# pwm_driver.net
KiCad netlist of a schematic drawn in EAGLE
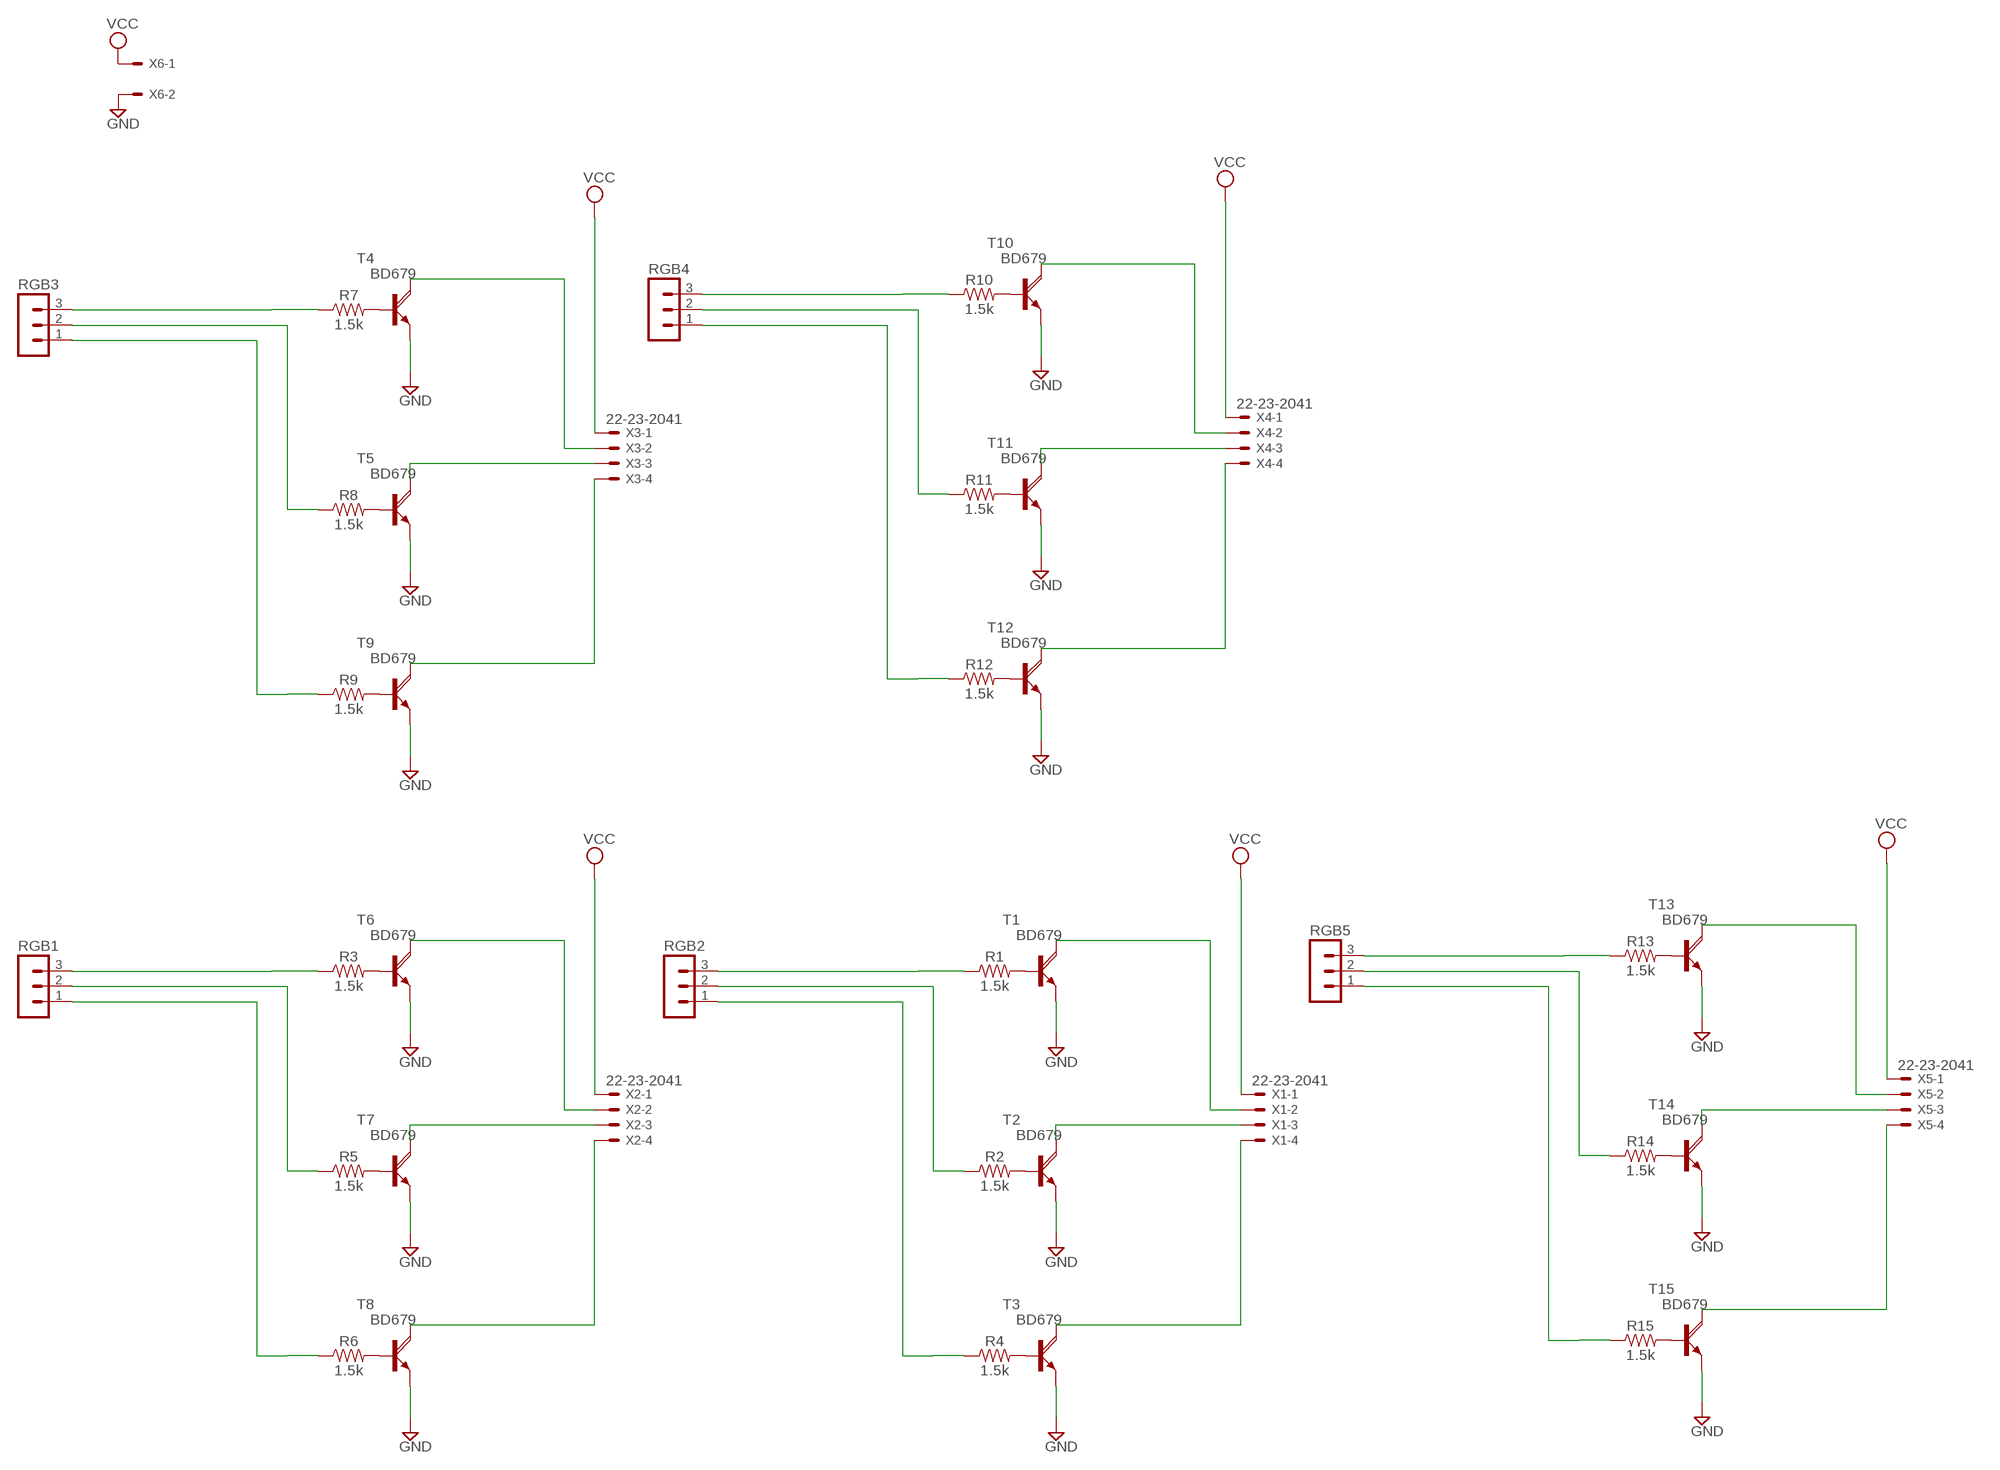
[diagram p0: schematic, sheet 1]

(export (version "E")
  (design (tool "Eeschema 10.0.6"))
  (components
    (comp (ref "R1")
      (value "1.5k")
      (footprint "eagle-import:0603")
      (libsource (lib "eagle-import") (part "1.5KOHM-0603-1/10W-1%"))
    )
    (comp (ref "R2")
      (value "1.5k")
      (footprint "eagle-import:0603")
      (libsource (lib "eagle-import") (part "1.5KOHM-0603-1/10W-1%"))
    )
    (comp (ref "R3")
      (value "1.5k")
      (footprint "eagle-import:0603")
      (libsource (lib "eagle-import") (part "1.5KOHM-0603-1/10W-1%"))
    )
    (comp (ref "R4")
      (value "1.5k")
      (footprint "eagle-import:0603")
      (libsource (lib "eagle-import") (part "1.5KOHM-0603-1/10W-1%"))
    )
    (comp (ref "R5")
      (value "1.5k")
      (footprint "eagle-import:0603")
      (libsource (lib "eagle-import") (part "1.5KOHM-0603-1/10W-1%"))
    )
    (comp (ref "R6")
      (value "1.5k")
      (footprint "eagle-import:0603")
      (libsource (lib "eagle-import") (part "1.5KOHM-0603-1/10W-1%"))
    )
    (comp (ref "R7")
      (value "1.5k")
      (footprint "eagle-import:0603")
      (libsource (lib "eagle-import") (part "1.5KOHM-0603-1/10W-1%"))
    )
    (comp (ref "R8")
      (value "1.5k")
      (footprint "eagle-import:0603")
      (libsource (lib "eagle-import") (part "1.5KOHM-0603-1/10W-1%"))
    )
    (comp (ref "R9")
      (value "1.5k")
      (footprint "eagle-import:0603")
      (libsource (lib "eagle-import") (part "1.5KOHM-0603-1/10W-1%"))
    )
    (comp (ref "R10")
      (value "1.5k")
      (footprint "eagle-import:0603")
      (libsource (lib "eagle-import") (part "1.5KOHM-0603-1/10W-1%"))
    )
    (comp (ref "R11")
      (value "1.5k")
      (footprint "eagle-import:0603")
      (libsource (lib "eagle-import") (part "1.5KOHM-0603-1/10W-1%"))
    )
    (comp (ref "R12")
      (value "1.5k")
      (footprint "eagle-import:0603")
      (libsource (lib "eagle-import") (part "1.5KOHM-0603-1/10W-1%"))
    )
    (comp (ref "R13")
      (value "1.5k")
      (footprint "eagle-import:0603")
      (libsource (lib "eagle-import") (part "1.5KOHM-0603-1/10W-1%"))
    )
    (comp (ref "R14")
      (value "1.5k")
      (footprint "eagle-import:0603")
      (libsource (lib "eagle-import") (part "1.5KOHM-0603-1/10W-1%"))
    )
    (comp (ref "R15")
      (value "1.5k")
      (footprint "eagle-import:0603")
      (libsource (lib "eagle-import") (part "1.5KOHM-0603-1/10W-1%"))
    )
    (comp (ref "RGB1")
      (value "MA03-1")
      (footprint "eagle-import:MA03-1")
      (libsource (lib "eagle-import") (part "MA03-1"))
    )
    (comp (ref "RGB2")
      (value "MA03-1")
      (footprint "eagle-import:MA03-1")
      (libsource (lib "eagle-import") (part "MA03-1"))
    )
    (comp (ref "RGB3")
      (value "MA03-1")
      (footprint "eagle-import:MA03-1")
      (libsource (lib "eagle-import") (part "MA03-1"))
    )
    (comp (ref "RGB4")
      (value "MA03-1")
      (footprint "eagle-import:MA03-1")
      (libsource (lib "eagle-import") (part "MA03-1"))
    )
    (comp (ref "RGB5")
      (value "MA03-1")
      (footprint "eagle-import:MA03-1")
      (libsource (lib "eagle-import") (part "MA03-1"))
    )
    (comp (ref "T1")
      (value "BD679")
      (footprint "eagle-import:TO126AV")
      (libsource (lib "eagle-import") (part "BD679"))
    )
    (comp (ref "T2")
      (value "BD679")
      (footprint "eagle-import:TO126AV")
      (libsource (lib "eagle-import") (part "BD679"))
    )
    (comp (ref "T3")
      (value "BD679")
      (footprint "eagle-import:TO126AV")
      (libsource (lib "eagle-import") (part "BD679"))
    )
    (comp (ref "T4")
      (value "BD679")
      (footprint "eagle-import:TO126AV")
      (libsource (lib "eagle-import") (part "BD679"))
    )
    (comp (ref "T5")
      (value "BD679")
      (footprint "eagle-import:TO126AV")
      (libsource (lib "eagle-import") (part "BD679"))
    )
    (comp (ref "T6")
      (value "BD679")
      (footprint "eagle-import:TO126AV")
      (libsource (lib "eagle-import") (part "BD679"))
    )
    (comp (ref "T7")
      (value "BD679")
      (footprint "eagle-import:TO126AV")
      (libsource (lib "eagle-import") (part "BD679"))
    )
    (comp (ref "T8")
      (value "BD679")
      (footprint "eagle-import:TO126AV")
      (libsource (lib "eagle-import") (part "BD679"))
    )
    (comp (ref "T9")
      (value "BD679")
      (footprint "eagle-import:TO126AV")
      (libsource (lib "eagle-import") (part "BD679"))
    )
    (comp (ref "T10")
      (value "BD679")
      (footprint "eagle-import:TO126AV")
      (libsource (lib "eagle-import") (part "BD679"))
    )
    (comp (ref "T11")
      (value "BD679")
      (footprint "eagle-import:TO126AV")
      (libsource (lib "eagle-import") (part "BD679"))
    )
    (comp (ref "T12")
      (value "BD679")
      (footprint "eagle-import:TO126AV")
      (libsource (lib "eagle-import") (part "BD679"))
    )
    (comp (ref "T13")
      (value "BD679")
      (footprint "eagle-import:TO126AV")
      (libsource (lib "eagle-import") (part "BD679"))
    )
    (comp (ref "T14")
      (value "BD679")
      (footprint "eagle-import:TO126AV")
      (libsource (lib "eagle-import") (part "BD679"))
    )
    (comp (ref "T15")
      (value "BD679")
      (footprint "eagle-import:TO126AV")
      (libsource (lib "eagle-import") (part "BD679"))
    )
    (comp (ref "X1")
      (value "22-23-2041")
      (footprint "eagle-import:22-23-2041")
      (fields (field (name "MF") "MOLEX"))
      (libsource (lib "eagle-import") (part "22-23-2041"))
    )
    (comp (ref "X2")
      (value "22-23-2041")
      (footprint "eagle-import:22-23-2041")
      (fields (field (name "MF") "MOLEX"))
      (libsource (lib "eagle-import") (part "22-23-2041"))
    )
    (comp (ref "X3")
      (value "22-23-2041")
      (footprint "eagle-import:22-23-2041")
      (fields (field (name "MF") "MOLEX"))
      (libsource (lib "eagle-import") (part "22-23-2041"))
    )
    (comp (ref "X4")
      (value "22-23-2041")
      (footprint "eagle-import:22-23-2041")
      (fields (field (name "MF") "MOLEX"))
      (libsource (lib "eagle-import") (part "22-23-2041"))
    )
    (comp (ref "X5")
      (value "22-23-2041")
      (footprint "eagle-import:22-23-2041")
      (fields (field (name "MF") "MOLEX"))
      (libsource (lib "eagle-import") (part "22-23-2041"))
    )
    (comp (ref "X6")
      (value "KK-156-2")
      (footprint "eagle-import:KK-156-2")
      (fields (field (name "MF") "MOLEX"))
      (libsource (lib "eagle-import") (part "KK-156-2"))
    )
  )
  (nets
    (net (code "1") (name "GND") (class "Default")
      (node (ref "T1") (pin "E") (pinfunction "E_E") (pintype "passive"))
      (node (ref "T10") (pin "E") (pinfunction "E_E") (pintype "passive"))
      (node (ref "T11") (pin "E") (pinfunction "E_E") (pintype "passive"))
      (node (ref "T12") (pin "E") (pinfunction "E_E") (pintype "passive"))
      (node (ref "T13") (pin "E") (pinfunction "E_E") (pintype "passive"))
      (node (ref "T14") (pin "E") (pinfunction "E_E") (pintype "passive"))
      (node (ref "T15") (pin "E") (pinfunction "E_E") (pintype "passive"))
      (node (ref "T2") (pin "E") (pinfunction "E_E") (pintype "passive"))
      (node (ref "T3") (pin "E") (pinfunction "E_E") (pintype "passive"))
      (node (ref "T4") (pin "E") (pinfunction "E_E") (pintype "passive"))
      (node (ref "T5") (pin "E") (pinfunction "E_E") (pintype "passive"))
      (node (ref "T6") (pin "E") (pinfunction "E_E") (pintype "passive"))
      (node (ref "T7") (pin "E") (pinfunction "E_E") (pintype "passive"))
      (node (ref "T8") (pin "E") (pinfunction "E_E") (pintype "passive"))
      (node (ref "T9") (pin "E") (pinfunction "E_E") (pintype "passive"))
      (node (ref "X6") (pin "2") (pinfunction "S_2") (pintype "passive"))
    )
    (net (code "2") (name "Net-(R1-Pad1)") (class "Default")
      (node (ref "R1") (pin "1") (pinfunction "1_1") (pintype "passive"))
      (node (ref "RGB2") (pin "3") (pinfunction "3_3") (pintype "passive"))
    )
    (net (code "3") (name "Net-(R1-Pad2)") (class "Default")
      (node (ref "R1") (pin "2") (pinfunction "2_2") (pintype "passive"))
      (node (ref "T1") (pin "B") (pinfunction "B_B") (pintype "passive"))
    )
    (net (code "4") (name "Net-(R2-Pad1)") (class "Default")
      (node (ref "R2") (pin "1") (pinfunction "1_1") (pintype "passive"))
      (node (ref "RGB2") (pin "2") (pinfunction "2_2") (pintype "passive"))
    )
    (net (code "5") (name "Net-(R2-Pad2)") (class "Default")
      (node (ref "R2") (pin "2") (pinfunction "2_2") (pintype "passive"))
      (node (ref "T2") (pin "B") (pinfunction "B_B") (pintype "passive"))
    )
    (net (code "6") (name "Net-(R3-Pad1)") (class "Default")
      (node (ref "R3") (pin "1") (pinfunction "1_1") (pintype "passive"))
      (node (ref "RGB1") (pin "3") (pinfunction "3_3") (pintype "passive"))
    )
    (net (code "7") (name "Net-(R3-Pad2)") (class "Default")
      (node (ref "R3") (pin "2") (pinfunction "2_2") (pintype "passive"))
      (node (ref "T6") (pin "B") (pinfunction "B_B") (pintype "passive"))
    )
    (net (code "8") (name "Net-(R4-Pad1)") (class "Default")
      (node (ref "R4") (pin "1") (pinfunction "1_1") (pintype "passive"))
      (node (ref "RGB2") (pin "1") (pinfunction "1_1") (pintype "passive"))
    )
    (net (code "9") (name "Net-(R4-Pad2)") (class "Default")
      (node (ref "R4") (pin "2") (pinfunction "2_2") (pintype "passive"))
      (node (ref "T3") (pin "B") (pinfunction "B_B") (pintype "passive"))
    )
    (net (code "10") (name "Net-(R5-Pad1)") (class "Default")
      (node (ref "R5") (pin "1") (pinfunction "1_1") (pintype "passive"))
      (node (ref "RGB1") (pin "2") (pinfunction "2_2") (pintype "passive"))
    )
    (net (code "11") (name "Net-(R5-Pad2)") (class "Default")
      (node (ref "R5") (pin "2") (pinfunction "2_2") (pintype "passive"))
      (node (ref "T7") (pin "B") (pinfunction "B_B") (pintype "passive"))
    )
    (net (code "12") (name "Net-(R6-Pad1)") (class "Default")
      (node (ref "R6") (pin "1") (pinfunction "1_1") (pintype "passive"))
      (node (ref "RGB1") (pin "1") (pinfunction "1_1") (pintype "passive"))
    )
    (net (code "13") (name "Net-(R6-Pad2)") (class "Default")
      (node (ref "R6") (pin "2") (pinfunction "2_2") (pintype "passive"))
      (node (ref "T8") (pin "B") (pinfunction "B_B") (pintype "passive"))
    )
    (net (code "14") (name "Net-(R7-Pad1)") (class "Default")
      (node (ref "R7") (pin "1") (pinfunction "1_1") (pintype "passive"))
      (node (ref "RGB3") (pin "3") (pinfunction "3_3") (pintype "passive"))
    )
    (net (code "15") (name "Net-(R7-Pad2)") (class "Default")
      (node (ref "R7") (pin "2") (pinfunction "2_2") (pintype "passive"))
      (node (ref "T4") (pin "B") (pinfunction "B_B") (pintype "passive"))
    )
    (net (code "16") (name "Net-(R8-Pad1)") (class "Default")
      (node (ref "R8") (pin "1") (pinfunction "1_1") (pintype "passive"))
      (node (ref "RGB3") (pin "2") (pinfunction "2_2") (pintype "passive"))
    )
    (net (code "17") (name "Net-(R8-Pad2)") (class "Default")
      (node (ref "R8") (pin "2") (pinfunction "2_2") (pintype "passive"))
      (node (ref "T5") (pin "B") (pinfunction "B_B") (pintype "passive"))
    )
    (net (code "18") (name "Net-(R9-Pad1)") (class "Default")
      (node (ref "R9") (pin "1") (pinfunction "1_1") (pintype "passive"))
      (node (ref "RGB3") (pin "1") (pinfunction "1_1") (pintype "passive"))
    )
    (net (code "19") (name "Net-(R9-Pad2)") (class "Default")
      (node (ref "R9") (pin "2") (pinfunction "2_2") (pintype "passive"))
      (node (ref "T9") (pin "B") (pinfunction "B_B") (pintype "passive"))
    )
    (net (code "20") (name "Net-(R10-Pad1)") (class "Default")
      (node (ref "R10") (pin "1") (pinfunction "1_1") (pintype "passive"))
      (node (ref "RGB4") (pin "3") (pinfunction "3_3") (pintype "passive"))
    )
    (net (code "21") (name "Net-(R10-Pad2)") (class "Default")
      (node (ref "R10") (pin "2") (pinfunction "2_2") (pintype "passive"))
      (node (ref "T10") (pin "B") (pinfunction "B_B") (pintype "passive"))
    )
    (net (code "22") (name "Net-(R11-Pad1)") (class "Default")
      (node (ref "R11") (pin "1") (pinfunction "1_1") (pintype "passive"))
      (node (ref "RGB4") (pin "2") (pinfunction "2_2") (pintype "passive"))
    )
    (net (code "23") (name "Net-(R11-Pad2)") (class "Default")
      (node (ref "R11") (pin "2") (pinfunction "2_2") (pintype "passive"))
      (node (ref "T11") (pin "B") (pinfunction "B_B") (pintype "passive"))
    )
    (net (code "24") (name "Net-(R12-Pad1)") (class "Default")
      (node (ref "R12") (pin "1") (pinfunction "1_1") (pintype "passive"))
      (node (ref "RGB4") (pin "1") (pinfunction "1_1") (pintype "passive"))
    )
    (net (code "25") (name "Net-(R12-Pad2)") (class "Default")
      (node (ref "R12") (pin "2") (pinfunction "2_2") (pintype "passive"))
      (node (ref "T12") (pin "B") (pinfunction "B_B") (pintype "passive"))
    )
    (net (code "26") (name "Net-(R13-Pad1)") (class "Default")
      (node (ref "R13") (pin "1") (pinfunction "1_1") (pintype "passive"))
      (node (ref "RGB5") (pin "3") (pinfunction "3_3") (pintype "passive"))
    )
    (net (code "27") (name "Net-(R13-Pad2)") (class "Default")
      (node (ref "R13") (pin "2") (pinfunction "2_2") (pintype "passive"))
      (node (ref "T13") (pin "B") (pinfunction "B_B") (pintype "passive"))
    )
    (net (code "28") (name "Net-(R14-Pad1)") (class "Default")
      (node (ref "R14") (pin "1") (pinfunction "1_1") (pintype "passive"))
      (node (ref "RGB5") (pin "2") (pinfunction "2_2") (pintype "passive"))
    )
    (net (code "29") (name "Net-(R14-Pad2)") (class "Default")
      (node (ref "R14") (pin "2") (pinfunction "2_2") (pintype "passive"))
      (node (ref "T14") (pin "B") (pinfunction "B_B") (pintype "passive"))
    )
    (net (code "30") (name "Net-(R15-Pad1)") (class "Default")
      (node (ref "R15") (pin "1") (pinfunction "1_1") (pintype "passive"))
      (node (ref "RGB5") (pin "1") (pinfunction "1_1") (pintype "passive"))
    )
    (net (code "31") (name "Net-(R15-Pad2)") (class "Default")
      (node (ref "R15") (pin "2") (pinfunction "2_2") (pintype "passive"))
      (node (ref "T15") (pin "B") (pinfunction "B_B") (pintype "passive"))
    )
    (net (code "32") (name "Net-(X1B-S)") (class "Default")
      (node (ref "T1") (pin "C") (pinfunction "C_C") (pintype "passive"))
      (node (ref "X1") (pin "2") (pinfunction "S_2") (pintype "passive"))
    )
    (net (code "33") (name "Net-(X1C-S)") (class "Default")
      (node (ref "T2") (pin "C") (pinfunction "C_C") (pintype "passive"))
      (node (ref "X1") (pin "3") (pinfunction "S_3") (pintype "passive"))
    )
    (net (code "34") (name "Net-(X1D-S)") (class "Default")
      (node (ref "T3") (pin "C") (pinfunction "C_C") (pintype "passive"))
      (node (ref "X1") (pin "4") (pinfunction "S_4") (pintype "passive"))
    )
    (net (code "35") (name "Net-(X2B-S)") (class "Default")
      (node (ref "T6") (pin "C") (pinfunction "C_C") (pintype "passive"))
      (node (ref "X2") (pin "2") (pinfunction "S_2") (pintype "passive"))
    )
    (net (code "36") (name "Net-(X2C-S)") (class "Default")
      (node (ref "T7") (pin "C") (pinfunction "C_C") (pintype "passive"))
      (node (ref "X2") (pin "3") (pinfunction "S_3") (pintype "passive"))
    )
    (net (code "37") (name "Net-(X2D-S)") (class "Default")
      (node (ref "T8") (pin "C") (pinfunction "C_C") (pintype "passive"))
      (node (ref "X2") (pin "4") (pinfunction "S_4") (pintype "passive"))
    )
    (net (code "38") (name "Net-(X3B-S)") (class "Default")
      (node (ref "T4") (pin "C") (pinfunction "C_C") (pintype "passive"))
      (node (ref "X3") (pin "2") (pinfunction "S_2") (pintype "passive"))
    )
    (net (code "39") (name "Net-(X3C-S)") (class "Default")
      (node (ref "T5") (pin "C") (pinfunction "C_C") (pintype "passive"))
      (node (ref "X3") (pin "3") (pinfunction "S_3") (pintype "passive"))
    )
    (net (code "40") (name "Net-(X3D-S)") (class "Default")
      (node (ref "T9") (pin "C") (pinfunction "C_C") (pintype "passive"))
      (node (ref "X3") (pin "4") (pinfunction "S_4") (pintype "passive"))
    )
    (net (code "41") (name "Net-(X4B-S)") (class "Default")
      (node (ref "T10") (pin "C") (pinfunction "C_C") (pintype "passive"))
      (node (ref "X4") (pin "2") (pinfunction "S_2") (pintype "passive"))
    )
    (net (code "42") (name "Net-(X4C-S)") (class "Default")
      (node (ref "T11") (pin "C") (pinfunction "C_C") (pintype "passive"))
      (node (ref "X4") (pin "3") (pinfunction "S_3") (pintype "passive"))
    )
    (net (code "43") (name "Net-(X4D-S)") (class "Default")
      (node (ref "T12") (pin "C") (pinfunction "C_C") (pintype "passive"))
      (node (ref "X4") (pin "4") (pinfunction "S_4") (pintype "passive"))
    )
    (net (code "44") (name "Net-(X5B-S)") (class "Default")
      (node (ref "T13") (pin "C") (pinfunction "C_C") (pintype "passive"))
      (node (ref "X5") (pin "2") (pinfunction "S_2") (pintype "passive"))
    )
    (net (code "45") (name "Net-(X5C-S)") (class "Default")
      (node (ref "T14") (pin "C") (pinfunction "C_C") (pintype "passive"))
      (node (ref "X5") (pin "3") (pinfunction "S_3") (pintype "passive"))
    )
    (net (code "46") (name "Net-(X5D-S)") (class "Default")
      (node (ref "T15") (pin "C") (pinfunction "C_C") (pintype "passive"))
      (node (ref "X5") (pin "4") (pinfunction "S_4") (pintype "passive"))
    )
    (net (code "47") (name "VCC") (class "Default")
      (node (ref "X1") (pin "1") (pinfunction "S_1") (pintype "passive"))
      (node (ref "X2") (pin "1") (pinfunction "S_1") (pintype "passive"))
      (node (ref "X3") (pin "1") (pinfunction "S_1") (pintype "passive"))
      (node (ref "X4") (pin "1") (pinfunction "S_1") (pintype "passive"))
      (node (ref "X5") (pin "1") (pinfunction "S_1") (pintype "passive"))
      (node (ref "X6") (pin "1") (pinfunction "S_1") (pintype "passive"))
    )
  )
)
